# rev02.net
KiCad netlist of a schematic drawn in EAGLE
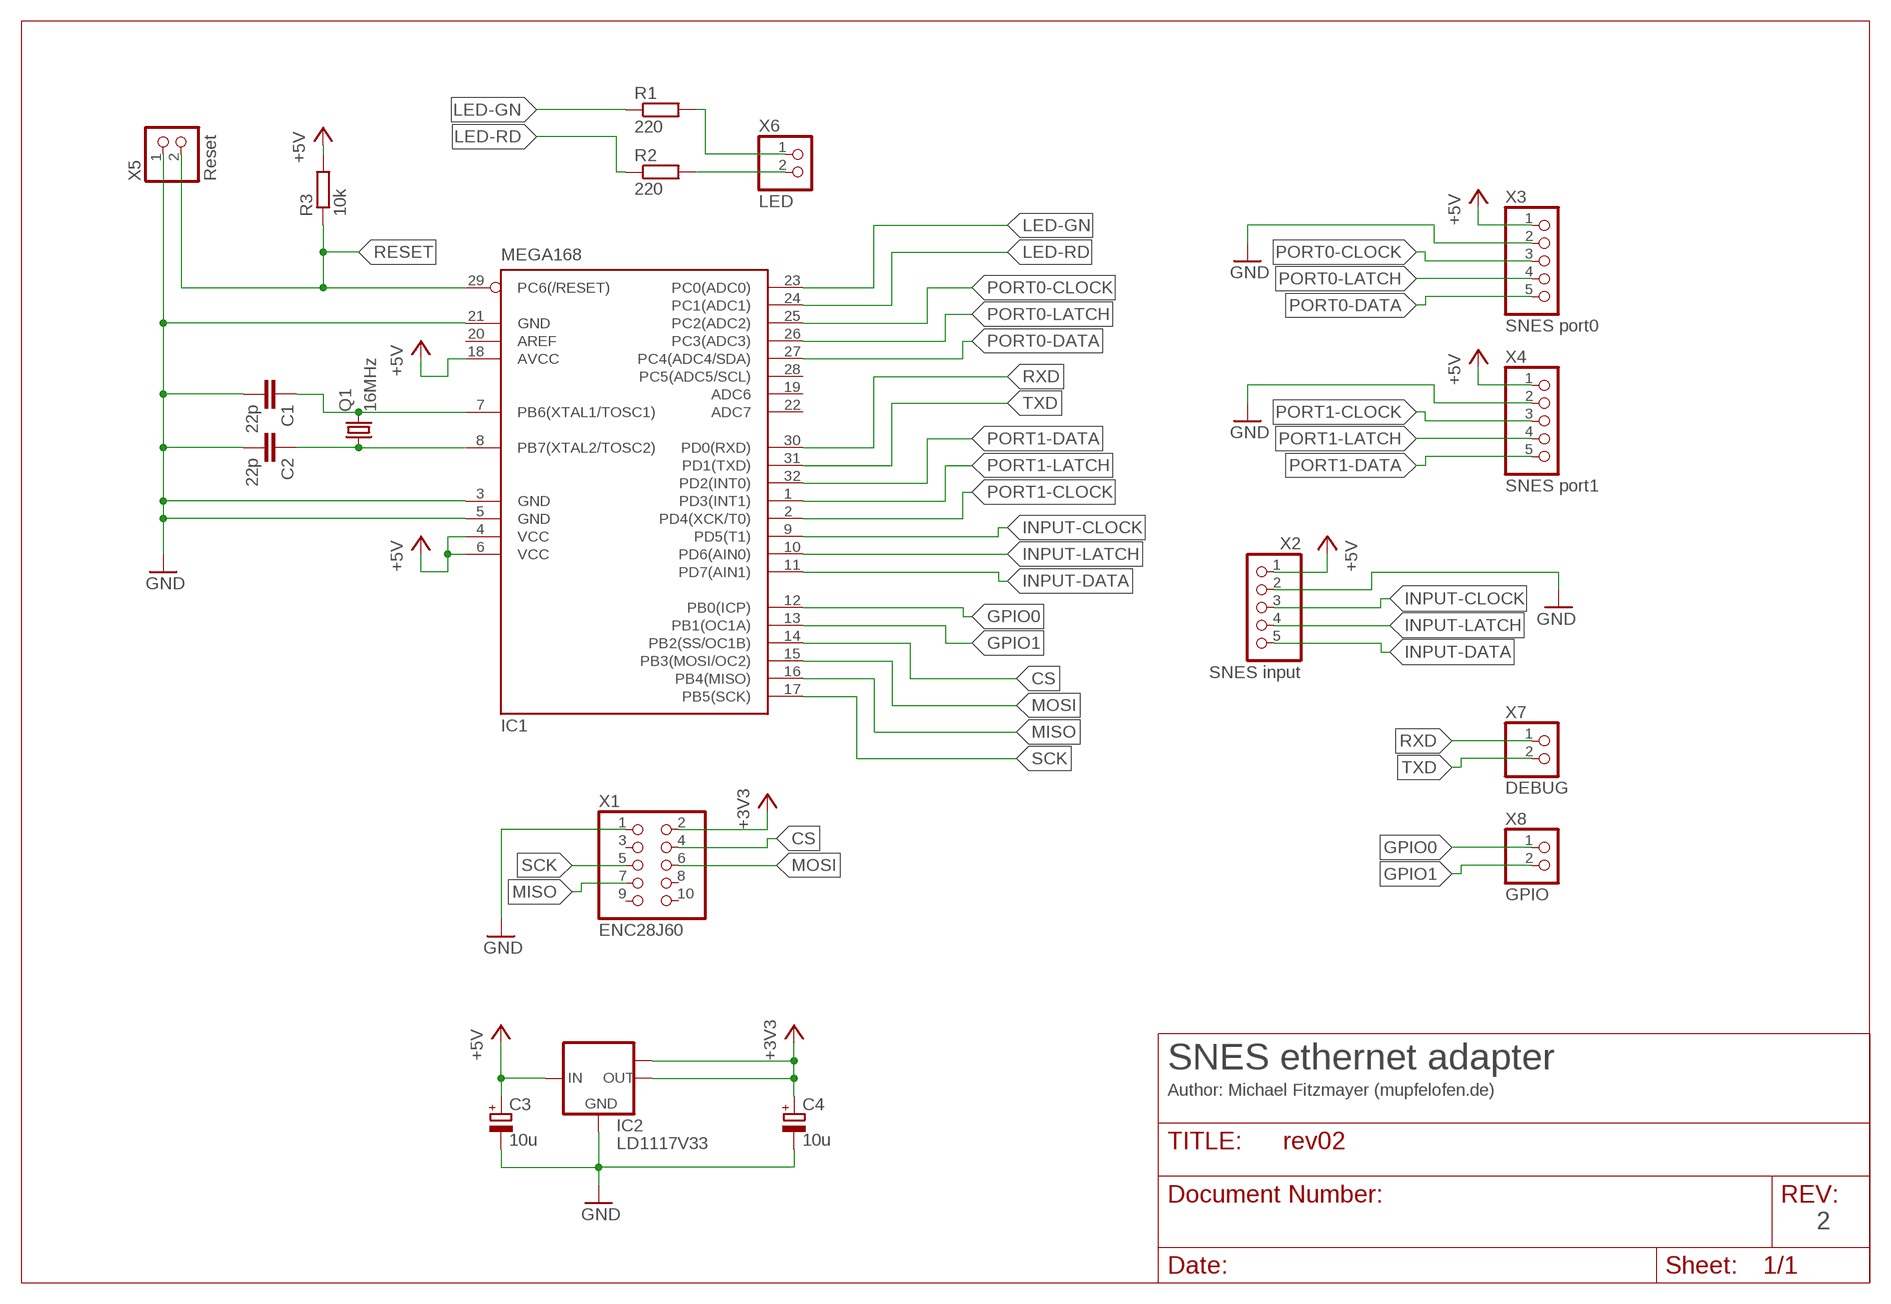
[diagram p0: schematic, sheet 1]

(export (version "E")
  (design (tool "Eeschema 10.0.6"))
  (components
    (comp (ref "C1")
      (value "22p")
      (footprint "eagle-import:C1206")
      (libsource (lib "eagle-import") (part "C-EUC1206"))
    )
    (comp (ref "C2")
      (value "22p")
      (footprint "eagle-import:C1206")
      (libsource (lib "eagle-import") (part "C-EUC1206"))
    )
    (comp (ref "C3")
      (value "10u")
      (footprint "eagle-import:C_6032-28R")
      (libsource (lib "eagle-import") (part "CPOL-EUC/6032-28R"))
    )
    (comp (ref "C4")
      (value "10u")
      (footprint "eagle-import:C_6032-28R")
      (libsource (lib "eagle-import") (part "CPOL-EUC/6032-28R"))
    )
    (comp (ref "IC1")
      (value "MEGA168")
      (footprint "eagle-import:TQFP32-08")
      (fields (field (name "MPN") "ATMEGA8-16AU"))
      (libsource (lib "eagle-import") (part "MEGA8-AI"))
    )
    (comp (ref "IC2")
      (value "LD1117V33")
      (footprint "eagle-import:SOT223")
      (libsource (lib "eagle-import") (part "LM1117MPX-3.3"))
    )
    (comp (ref "Q1")
      (value "16MHz")
      (footprint "eagle-import:SM49")
      (libsource (lib "eagle-import") (part "CRYSTALSM49"))
    )
    (comp (ref "R1")
      (value "220")
      (footprint "eagle-import:R1206")
      (libsource (lib "eagle-import") (part "R-EU_R1206"))
    )
    (comp (ref "R2")
      (value "220")
      (footprint "eagle-import:R1206")
      (libsource (lib "eagle-import") (part "R-EU_R1206"))
    )
    (comp (ref "R3")
      (value "10k")
      (footprint "eagle-import:R1206")
      (libsource (lib "eagle-import") (part "R-EU_R1206"))
    )
    (comp (ref "X1")
      (value "ENC28J60")
      (footprint "eagle-import:2X05SMD")
      (libsource (lib "eagle-import") (part "PINHD-2X5_2.54-SMD"))
    )
    (comp (ref "X2")
      (value "SNES input")
      (footprint "eagle-import:1X05SMD")
      (libsource (lib "eagle-import") (part "PINHD-1X5_2.54-SMD"))
    )
    (comp (ref "X3")
      (value "SNES port0")
      (footprint "eagle-import:1X05SMD")
      (libsource (lib "eagle-import") (part "PINHD-1X5_2.54-SMD"))
    )
    (comp (ref "X4")
      (value "SNES port1")
      (footprint "eagle-import:1X05SMD")
      (libsource (lib "eagle-import") (part "PINHD-1X5_2.54-SMD"))
    )
    (comp (ref "X5")
      (value "Reset")
      (footprint "eagle-import:1X02SMD")
      (libsource (lib "eagle-import") (part "PINHD-1X2_2.54-SMD"))
    )
    (comp (ref "X6")
      (value "LED")
      (footprint "eagle-import:1X02SMD")
      (libsource (lib "eagle-import") (part "PINHD-1X2_2.54-SMD"))
    )
    (comp (ref "X7")
      (value "DEBUG")
      (footprint "eagle-import:1X02SMD")
      (libsource (lib "eagle-import") (part "PINHD-1X2_2.54-SMD"))
    )
    (comp (ref "X8")
      (value "GPIO")
      (footprint "eagle-import:1X02SMD")
      (libsource (lib "eagle-import") (part "PINHD-1X2_2.54-SMD"))
    )
  )
  (nets
    (net (code "1") (name "+3V3") (class "Default")
      (node (ref "C4") (pin "+") (pinfunction "+_+") (pintype "passive"))
      (node (ref "IC2") (pin "2") (pinfunction "OUT_2") (pintype "passive"))
      (node (ref "IC2") (pin "TAB") (pinfunction "OUT1_TAB") (pintype "passive"))
      (node (ref "X1") (pin "2") (pinfunction "2_2") (pintype "passive"))
    )
    (net (code "2") (name "+5V") (class "Default")
      (node (ref "C3") (pin "+") (pinfunction "+_+") (pintype "passive"))
      (node (ref "IC1") (pin "18") (pinfunction "AVCC_18") (pintype "power_in"))
      (node (ref "IC1") (pin "4") (pinfunction "VCC_4") (pintype "power_in"))
      (node (ref "IC1") (pin "6") (pinfunction "VCC_6") (pintype "power_in"))
      (node (ref "IC2") (pin "3") (pinfunction "IN_3") (pintype "input"))
      (node (ref "R3") (pin "2") (pinfunction "2_2") (pintype "passive"))
      (node (ref "X2") (pin "1") (pinfunction "1_1") (pintype "passive"))
      (node (ref "X3") (pin "1") (pinfunction "1_1") (pintype "passive"))
      (node (ref "X4") (pin "1") (pinfunction "1_1") (pintype "passive"))
    )
    (net (code "3") (name "CS") (class "Default")
      (node (ref "IC1") (pin "14") (pinfunction "PB2(SS/OC1B)_14") (pintype "bidirectional"))
      (node (ref "X1") (pin "4") (pinfunction "4_4") (pintype "passive"))
    )
    (net (code "4") (name "GND") (class "Default")
      (node (ref "C1") (pin "2") (pinfunction "2_2") (pintype "passive"))
      (node (ref "C2") (pin "2") (pinfunction "2_2") (pintype "passive"))
      (node (ref "C3") (pin "-") (pinfunction "-_-") (pintype "passive"))
      (node (ref "C4") (pin "-") (pinfunction "-_-") (pintype "passive"))
      (node (ref "IC1") (pin "21") (pinfunction "GND_21") (pintype "power_in"))
      (node (ref "IC1") (pin "3") (pinfunction "GND_3") (pintype "power_in"))
      (node (ref "IC1") (pin "5") (pinfunction "GND_5") (pintype "power_in"))
      (node (ref "IC2") (pin "1") (pinfunction "GND_1") (pintype "input"))
      (node (ref "X1") (pin "1") (pinfunction "1_1") (pintype "passive"))
      (node (ref "X2") (pin "2") (pinfunction "2_2") (pintype "passive"))
      (node (ref "X3") (pin "2") (pinfunction "2_2") (pintype "passive"))
      (node (ref "X4") (pin "2") (pinfunction "2_2") (pintype "passive"))
      (node (ref "X5") (pin "1") (pinfunction "1_1") (pintype "passive"))
    )
    (net (code "5") (name "GPIO0") (class "Default")
      (node (ref "IC1") (pin "12") (pinfunction "PB0(ICP)_12") (pintype "bidirectional"))
      (node (ref "X8") (pin "1") (pinfunction "1_1") (pintype "passive"))
    )
    (net (code "6") (name "GPIO1") (class "Default")
      (node (ref "IC1") (pin "13") (pinfunction "PB1(OC1A)_13") (pintype "bidirectional"))
      (node (ref "X8") (pin "2") (pinfunction "2_2") (pintype "passive"))
    )
    (net (code "7") (name "INPUT-CLOCK") (class "Default")
      (node (ref "IC1") (pin "9") (pinfunction "PD5(T1)_9") (pintype "bidirectional"))
      (node (ref "X2") (pin "3") (pinfunction "3_3") (pintype "passive"))
    )
    (net (code "8") (name "INPUT-DATA") (class "Default")
      (node (ref "IC1") (pin "11") (pinfunction "PD7(AIN1)_11") (pintype "bidirectional"))
      (node (ref "X2") (pin "5") (pinfunction "5_5") (pintype "passive"))
    )
    (net (code "9") (name "INPUT-LATCH") (class "Default")
      (node (ref "IC1") (pin "10") (pinfunction "PD6(AIN0)_10") (pintype "bidirectional"))
      (node (ref "X2") (pin "4") (pinfunction "4_4") (pintype "passive"))
    )
    (net (code "10") (name "LED-GN") (class "Default")
      (node (ref "IC1") (pin "23") (pinfunction "PC0(ADC0)_23") (pintype "bidirectional"))
      (node (ref "R1") (pin "1") (pinfunction "1_1") (pintype "passive"))
    )
    (net (code "11") (name "LED-RD") (class "Default")
      (node (ref "IC1") (pin "24") (pinfunction "PC1(ADC1)_24") (pintype "bidirectional"))
      (node (ref "R2") (pin "1") (pinfunction "1_1") (pintype "passive"))
    )
    (net (code "12") (name "MISO") (class "Default")
      (node (ref "IC1") (pin "16") (pinfunction "PB4(MISO)_16") (pintype "bidirectional"))
      (node (ref "X1") (pin "7") (pinfunction "7_7") (pintype "passive"))
    )
    (net (code "13") (name "MOSI") (class "Default")
      (node (ref "IC1") (pin "15") (pinfunction "PB3(MOSI/OC2)_15") (pintype "bidirectional"))
      (node (ref "X1") (pin "6") (pinfunction "6_6") (pintype "passive"))
    )
    (net (code "14") (name "Net-(IC1-PB6(XTAL1{slash}TOSC1))") (class "Default")
      (node (ref "C1") (pin "1") (pinfunction "1_1") (pintype "passive"))
      (node (ref "IC1") (pin "7") (pinfunction "PB6(XTAL1/TOSC1)_7") (pintype "bidirectional"))
      (node (ref "Q1") (pin "2") (pinfunction "2_2") (pintype "passive"))
    )
    (net (code "15") (name "Net-(IC1-PB7(XTAL2{slash}TOSC2))") (class "Default")
      (node (ref "C2") (pin "1") (pinfunction "1_1") (pintype "passive"))
      (node (ref "IC1") (pin "8") (pinfunction "PB7(XTAL2/TOSC2)_8") (pintype "bidirectional"))
      (node (ref "Q1") (pin "1") (pinfunction "1_1") (pintype "passive"))
    )
    (net (code "16") (name "Net-(R1-Pad2)") (class "Default")
      (node (ref "R1") (pin "2") (pinfunction "2_2") (pintype "passive"))
      (node (ref "X6") (pin "1") (pinfunction "1_1") (pintype "passive"))
    )
    (net (code "17") (name "Net-(R2-Pad2)") (class "Default")
      (node (ref "R2") (pin "2") (pinfunction "2_2") (pintype "passive"))
      (node (ref "X6") (pin "2") (pinfunction "2_2") (pintype "passive"))
    )
    (net (code "18") (name "PORT0-CLOCK") (class "Default")
      (node (ref "IC1") (pin "25") (pinfunction "PC2(ADC2)_25") (pintype "bidirectional"))
      (node (ref "X3") (pin "3") (pinfunction "3_3") (pintype "passive"))
    )
    (net (code "19") (name "PORT0-DATA") (class "Default")
      (node (ref "IC1") (pin "27") (pinfunction "PC4(ADC4/SDA)_27") (pintype "bidirectional"))
      (node (ref "X3") (pin "5") (pinfunction "5_5") (pintype "passive"))
    )
    (net (code "20") (name "PORT0-LATCH") (class "Default")
      (node (ref "IC1") (pin "26") (pinfunction "PC3(ADC3)_26") (pintype "bidirectional"))
      (node (ref "X3") (pin "4") (pinfunction "4_4") (pintype "passive"))
    )
    (net (code "21") (name "PORT1-CLOCK") (class "Default")
      (node (ref "IC1") (pin "2") (pinfunction "PD4(XCK/T0)_2") (pintype "bidirectional"))
      (node (ref "X4") (pin "3") (pinfunction "3_3") (pintype "passive"))
    )
    (net (code "22") (name "PORT1-DATA") (class "Default")
      (node (ref "IC1") (pin "32") (pinfunction "PD2(INT0)_32") (pintype "bidirectional"))
      (node (ref "X4") (pin "5") (pinfunction "5_5") (pintype "passive"))
    )
    (net (code "23") (name "PORT1-LATCH") (class "Default")
      (node (ref "IC1") (pin "1") (pinfunction "PD3(INT1)_1") (pintype "bidirectional"))
      (node (ref "X4") (pin "4") (pinfunction "4_4") (pintype "passive"))
    )
    (net (code "24") (name "RESET") (class "Default")
      (node (ref "IC1") (pin "29") (pinfunction "PC6(/RESET)_29") (pintype "bidirectional"))
      (node (ref "R3") (pin "1") (pinfunction "1_1") (pintype "passive"))
      (node (ref "X5") (pin "2") (pinfunction "2_2") (pintype "passive"))
    )
    (net (code "25") (name "RXD") (class "Default")
      (node (ref "IC1") (pin "30") (pinfunction "PD0(RXD)_30") (pintype "bidirectional"))
      (node (ref "X7") (pin "1") (pinfunction "1_1") (pintype "passive"))
    )
    (net (code "26") (name "SCK") (class "Default")
      (node (ref "IC1") (pin "17") (pinfunction "PB5(SCK)_17") (pintype "bidirectional"))
      (node (ref "X1") (pin "5") (pinfunction "5_5") (pintype "passive"))
    )
    (net (code "27") (name "TXD") (class "Default")
      (node (ref "IC1") (pin "31") (pinfunction "PD1(TXD)_31") (pintype "bidirectional"))
      (node (ref "X7") (pin "2") (pinfunction "2_2") (pintype "passive"))
    )
    (net (code "28") (name "unconnected-(IC1-ADC6-Pad19)") (class "Default")
      (node (ref "IC1") (pin "19") (pinfunction "ADC6_19") (pintype "bidirectional"))
    )
    (net (code "29") (name "unconnected-(IC1-ADC7-Pad22)") (class "Default")
      (node (ref "IC1") (pin "22") (pinfunction "ADC7_22") (pintype "bidirectional"))
    )
    (net (code "30") (name "unconnected-(IC1-AREF-Pad20)") (class "Default")
      (node (ref "IC1") (pin "20") (pinfunction "AREF_20") (pintype "passive"))
    )
    (net (code "31") (name "unconnected-(IC1-PC5(ADC5{slash}SCL)-Pad28)") (class "Default")
      (node (ref "IC1") (pin "28") (pinfunction "PC5(ADC5/SCL)_28") (pintype "bidirectional"))
    )
    (net (code "32") (name "unconnected-(X1-Pad3)") (class "Default")
      (node (ref "X1") (pin "3") (pinfunction "3_3") (pintype "passive"))
    )
    (net (code "33") (name "unconnected-(X1-Pad8)") (class "Default")
      (node (ref "X1") (pin "8") (pinfunction "8_8") (pintype "passive"))
    )
    (net (code "34") (name "unconnected-(X1-Pad9)") (class "Default")
      (node (ref "X1") (pin "9") (pinfunction "9_9") (pintype "passive"))
    )
    (net (code "35") (name "unconnected-(X1-Pad10)") (class "Default")
      (node (ref "X1") (pin "10") (pinfunction "10_10") (pintype "passive"))
    )
  )
)
